# new_york_rev_B.net
KiCad netlist of a schematic drawn in EAGLE
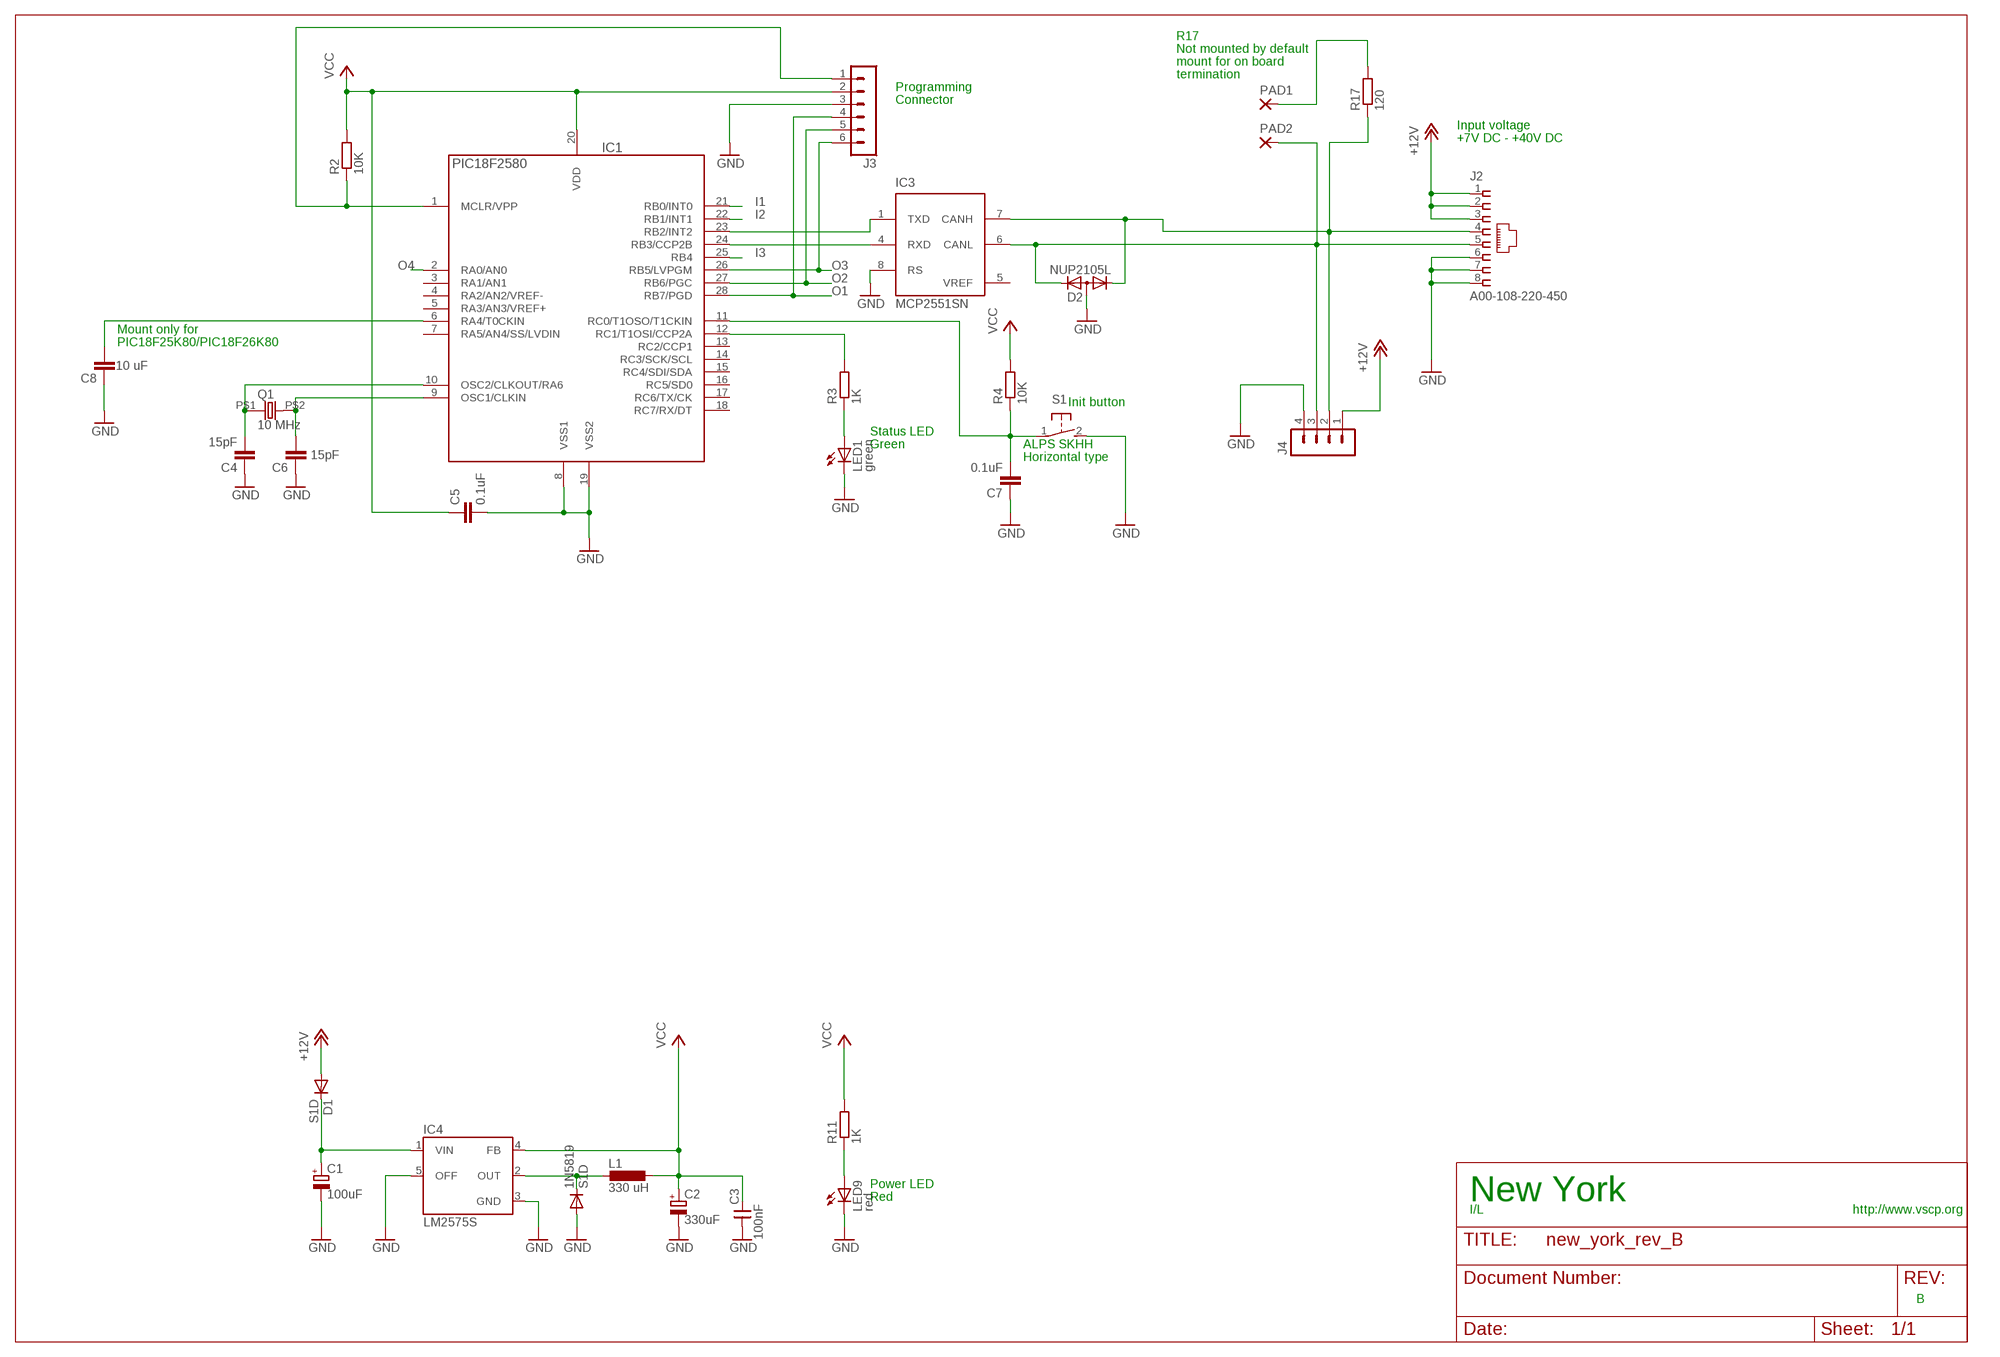
[diagram p0: schematic, sheet 1]

(export (version "E")
  (design (tool "Eeschema 10.0.6"))
  (components
    (comp (ref "1N5819")
      (value "S1D")
      (footprint "eagle-import:SOD123")
      (libsource (lib "eagle-import") (part "DIODE-SOD123"))
    )
    (comp (ref "C1")
      (value "100uF")
      (footprint "eagle-import:PANASONIC_D")
      (libsource (lib "eagle-import") (part "CPOL-EUD"))
    )
    (comp (ref "C2")
      (value "330uF")
      (footprint "eagle-import:PANASONIC_D")
      (libsource (lib "eagle-import") (part "CPOL-EUD"))
    )
    (comp (ref "C3")
      (value "100nF")
      (footprint "eagle-import:0805")
      (libsource (lib "eagle-import") (part "CNP-0805"))
    )
    (comp (ref "C4")
      (value "15pF")
      (footprint "eagle-import:C0805")
      (libsource (lib "eagle-import") (part "C-EUC0805"))
    )
    (comp (ref "C5")
      (value "0.1uF")
      (footprint "eagle-import:C0805")
      (libsource (lib "eagle-import") (part "C-EUC0805"))
    )
    (comp (ref "C6")
      (value "15pF")
      (footprint "eagle-import:C0805")
      (libsource (lib "eagle-import") (part "C-EUC0805"))
    )
    (comp (ref "C7")
      (value "0.1uF")
      (footprint "eagle-import:C0805")
      (libsource (lib "eagle-import") (part "C-EUC0805"))
    )
    (comp (ref "C8")
      (value "10 uF")
      (footprint "eagle-import:C0805")
      (libsource (lib "eagle-import") (part "C-EUC0805"))
    )
    (comp (ref "D1")
      (value "S1D")
      (footprint "eagle-import:SOD123")
      (libsource (lib "eagle-import") (part "DIODE-SOD123"))
    )
    (comp (ref "D2")
      (value "NUP2105L")
      (footprint "eagle-import:SOT23")
      (libsource (lib "eagle-import") (part "DIODE-2CA|ACSOT23"))
    )
    (comp (ref "IC1")
      (value "PIC18F2580")
      (footprint "eagle-import:SO28")
      (libsource (lib "eagle-import") (part "PIC18F252-?I/SOL"))
    )
    (comp (ref "IC3")
      (value "MCP2551SN")
      (footprint "eagle-import:SO-08")
      (libsource (lib "eagle-import") (part "MCP2551SN"))
    )
    (comp (ref "IC4")
      (value "LM2575S")
      (footprint "eagle-import:TO263-5")
      (libsource (lib "eagle-import") (part "LM2575S"))
    )
    (comp (ref "J2")
      (value "A00-108-220-450")
      (footprint "eagle-import:RJ-45")
      (libsource (lib "eagle-import") (part "A00-108-220-450"))
    )
    (comp (ref "J3")
      (value "MA06-1")
      (footprint "eagle-import:MA06-1")
      (libsource (lib "eagle-import") (part "MA06-1"))
    )
    (comp (ref "J4")
      (value "MA04-1")
      (footprint "eagle-import:MA04-1")
      (libsource (lib "eagle-import") (part "MA04-1"))
    )
    (comp (ref "L1")
      (value "330 uH")
      (footprint "eagle-import:DO3316P")
      (libsource (lib "eagle-import") (part "DO3316P"))
    )
    (comp (ref "LED1")
      (value "green")
      (footprint "eagle-import:CHIP-LED0805")
      (libsource (lib "eagle-import") (part "LEDCHIP-LED0805"))
    )
    (comp (ref "LED9")
      (value "red")
      (footprint "eagle-import:CHIP-LED0805")
      (libsource (lib "eagle-import") (part "LEDCHIP-LED0805"))
    )
    (comp (ref "PAD1")
      (value "1,6/0,8")
      (footprint "eagle-import:1,6_0,8")
      (libsource (lib "eagle-import") (part "1,6/0,8"))
    )
    (comp (ref "PAD2")
      (value "1,6/0,8")
      (footprint "eagle-import:1,6_0,8")
      (libsource (lib "eagle-import") (part "1,6/0,8"))
    )
    (comp (ref "Q1")
      (value "10 MHz")
      (footprint "eagle-import:9C")
      (libsource (lib "eagle-import") (part "HC-49S"))
    )
    (comp (ref "R2")
      (value "10K")
      (footprint "eagle-import:R0805")
      (libsource (lib "eagle-import") (part "R-EU_R0805"))
    )
    (comp (ref "R3")
      (value "1K")
      (footprint "eagle-import:R0805")
      (libsource (lib "eagle-import") (part "R-EU_R0805"))
    )
    (comp (ref "R4")
      (value "10K")
      (footprint "eagle-import:R0805")
      (libsource (lib "eagle-import") (part "R-EU_R0805"))
    )
    (comp (ref "R11")
      (value "1K")
      (footprint "eagle-import:R0805")
      (libsource (lib "eagle-import") (part "R-EU_R0805"))
    )
    (comp (ref "R17")
      (value "120")
      (footprint "eagle-import:R0805")
      (libsource (lib "eagle-import") (part "R-EU_R0805"))
    )
    (comp (ref "S1")
      (value "31-XX")
      (footprint "eagle-import:B3F-31XX")
      (fields (field (name "MPN") "B3F-3100"))
      (libsource (lib "eagle-import") (part "31-XX"))
    )
  )
  (nets
    (net (code "1") (name "+12V") (class "Default")
      (node (ref "D1") (pin "A") (pinfunction "A_A") (pintype "passive"))
      (node (ref "J2") (pin "1") (pinfunction "1_1") (pintype "passive"))
      (node (ref "J2") (pin "2") (pinfunction "2_2") (pintype "passive"))
      (node (ref "J2") (pin "3") (pinfunction "3_3") (pintype "passive"))
      (node (ref "J4") (pin "1") (pinfunction "1_1") (pintype "passive"))
    )
    (net (code "2") (name "/I1") (class "Default")
      (node (ref "IC1") (pin "21") (pinfunction "RB0/INT0_21") (pintype "bidirectional"))
    )
    (net (code "3") (name "/I2") (class "Default")
      (node (ref "IC1") (pin "22") (pinfunction "RB1/INT1_22") (pintype "bidirectional"))
    )
    (net (code "4") (name "/I3") (class "Default")
      (node (ref "IC1") (pin "25") (pinfunction "RB4_25") (pintype "bidirectional"))
    )
    (net (code "5") (name "/O1") (class "Default")
      (node (ref "IC1") (pin "28") (pinfunction "RB7/PGD_28") (pintype "bidirectional"))
      (node (ref "J3") (pin "4") (pinfunction "4_4") (pintype "passive"))
    )
    (net (code "6") (name "/O2") (class "Default")
      (node (ref "IC1") (pin "27") (pinfunction "RB6/PGC_27") (pintype "bidirectional"))
      (node (ref "J3") (pin "5") (pinfunction "5_5") (pintype "passive"))
    )
    (net (code "7") (name "/O3") (class "Default")
      (node (ref "IC1") (pin "26") (pinfunction "RB5/LVPGM_26") (pintype "bidirectional"))
      (node (ref "J3") (pin "6") (pinfunction "6_6") (pintype "passive"))
    )
    (net (code "8") (name "/O4") (class "Default")
      (node (ref "IC1") (pin "2") (pinfunction "RA0/AN0_2") (pintype "bidirectional"))
    )
    (net (code "9") (name "/VREF") (class "Default")
      (node (ref "IC3") (pin "5") (pinfunction "VREF_5") (pintype "power_in"))
    )
    (net (code "10") (name "GND") (class "Default")
      (node (ref "1N5819") (pin "A") (pinfunction "A_A") (pintype "passive"))
      (node (ref "C1") (pin "-") (pinfunction "-_-") (pintype "passive"))
      (node (ref "C2") (pin "-") (pinfunction "-_-") (pintype "passive"))
      (node (ref "C3") (pin "1") (pinfunction "1_1") (pintype "passive"))
      (node (ref "C4") (pin "1") (pinfunction "1_1") (pintype "passive"))
      (node (ref "C5") (pin "2") (pinfunction "2_2") (pintype "passive"))
      (node (ref "C6") (pin "1") (pinfunction "1_1") (pintype "passive"))
      (node (ref "C7") (pin "1") (pinfunction "1_1") (pintype "passive"))
      (node (ref "C8") (pin "1") (pinfunction "1_1") (pintype "passive"))
      (node (ref "D2") (pin "3") (pinfunction "A_3") (pintype "passive"))
      (node (ref "IC1") (pin "19") (pinfunction "VSS2_19") (pintype "power_in"))
      (node (ref "IC1") (pin "8") (pinfunction "VSS1_8") (pintype "power_in"))
      (node (ref "IC3") (pin "8") (pinfunction "RS_8") (pintype "input"))
      (node (ref "IC4") (pin "3") (pinfunction "GND_3") (pintype "power_in"))
      (node (ref "IC4") (pin "5") (pinfunction "OFF_5") (pintype "input"))
      (node (ref "J2") (pin "6") (pinfunction "6_6") (pintype "passive"))
      (node (ref "J2") (pin "7") (pinfunction "7_7") (pintype "passive"))
      (node (ref "J2") (pin "8") (pinfunction "8_8") (pintype "passive"))
      (node (ref "J3") (pin "3") (pinfunction "3_3") (pintype "passive"))
      (node (ref "J4") (pin "4") (pinfunction "4_4") (pintype "passive"))
      (node (ref "LED1") (pin "C") (pinfunction "C_C") (pintype "passive"))
      (node (ref "LED9") (pin "C") (pinfunction "C_C") (pintype "passive"))
      (node (ref "S1") (pin "2") (pinfunction "S_2") (pintype "passive"))
    )
    (net (code "11") (name "Net-(D2-K1)") (class "Default")
      (node (ref "D2") (pin "1") (pinfunction "K1_1") (pintype "passive"))
      (node (ref "IC3") (pin "7") (pinfunction "CANH_7") (pintype "bidirectional"))
      (node (ref "J2") (pin "4") (pinfunction "4_4") (pintype "passive"))
      (node (ref "J4") (pin "2") (pinfunction "2_2") (pintype "passive"))
      (node (ref "R17") (pin "1") (pinfunction "1_1") (pintype "passive"))
    )
    (net (code "12") (name "Net-(D2-K2)") (class "Default")
      (node (ref "D2") (pin "2") (pinfunction "K2_2") (pintype "passive"))
      (node (ref "IC3") (pin "6") (pinfunction "CANL_6") (pintype "bidirectional"))
      (node (ref "J2") (pin "5") (pinfunction "5_5") (pintype "passive"))
      (node (ref "J4") (pin "3") (pinfunction "3_3") (pintype "passive"))
      (node (ref "PAD2") (pin "1") (pinfunction "P_1") (pintype "passive"))
    )
    (net (code "13") (name "Net-(IC1-MCLR{slash}VPP)") (class "Default")
      (node (ref "IC1") (pin "1") (pinfunction "MCLR/VPP_1") (pintype "input"))
      (node (ref "J3") (pin "1") (pinfunction "1_1") (pintype "passive"))
      (node (ref "R2") (pin "1") (pinfunction "1_1") (pintype "passive"))
    )
    (net (code "14") (name "Net-(IC1-OSC1{slash}CLKIN)") (class "Default")
      (node (ref "C6") (pin "2") (pinfunction "2_2") (pintype "passive"))
      (node (ref "IC1") (pin "9") (pinfunction "OSC1/CLKIN_9") (pintype "input"))
      (node (ref "Q1") (pin "P$2") (pinfunction "2_P$2") (pintype "passive"))
    )
    (net (code "15") (name "Net-(IC1-OSC2{slash}CLKOUT{slash}RA6)") (class "Default")
      (node (ref "C4") (pin "2") (pinfunction "2_2") (pintype "passive"))
      (node (ref "IC1") (pin "10") (pinfunction "OSC2/CLKOUT/RA6_10") (pintype "output"))
      (node (ref "Q1") (pin "P$1") (pinfunction "1_P$1") (pintype "passive"))
    )
    (net (code "16") (name "Net-(IC1-RA4{slash}T0CKIN)") (class "Default")
      (node (ref "C8") (pin "2") (pinfunction "2_2") (pintype "passive"))
      (node (ref "IC1") (pin "6") (pinfunction "RA4/T0CKIN_6") (pintype "open_collector"))
    )
    (net (code "17") (name "Net-(IC1-RB2{slash}INT2)") (class "Default")
      (node (ref "IC1") (pin "23") (pinfunction "RB2/INT2_23") (pintype "bidirectional"))
      (node (ref "IC3") (pin "1") (pinfunction "TXD_1") (pintype "input"))
    )
    (net (code "18") (name "Net-(IC1-RB3{slash}CCP2B)") (class "Default")
      (node (ref "IC1") (pin "24") (pinfunction "RB3/CCP2B_24") (pintype "bidirectional"))
      (node (ref "IC3") (pin "4") (pinfunction "RXD_4") (pintype "output"))
    )
    (net (code "19") (name "Net-(IC1-RC0{slash}T1OSO{slash}T1CKIN)") (class "Default")
      (node (ref "C7") (pin "2") (pinfunction "2_2") (pintype "passive"))
      (node (ref "IC1") (pin "11") (pinfunction "RC0/T1OSO/T1CKIN_11") (pintype "bidirectional"))
      (node (ref "R4") (pin "1") (pinfunction "1_1") (pintype "passive"))
      (node (ref "S1") (pin "1") (pinfunction "P_1") (pintype "passive"))
    )
    (net (code "20") (name "Net-(IC1-RC1{slash}T1OSI{slash}CCP2A)") (class "Default")
      (node (ref "IC1") (pin "12") (pinfunction "RC1/T1OSI/CCP2A_12") (pintype "bidirectional"))
      (node (ref "R3") (pin "2") (pinfunction "2_2") (pintype "passive"))
    )
    (net (code "21") (name "Net-(IC4-OUT)") (class "Default")
      (node (ref "1N5819") (pin "C") (pinfunction "C_C") (pintype "passive"))
      (node (ref "IC4") (pin "2") (pinfunction "OUT_2") (pintype "output"))
      (node (ref "L1") (pin "1") (pinfunction "1_1") (pintype "passive"))
    )
    (net (code "22") (name "Net-(IC4-VIN)") (class "Default")
      (node (ref "C1") (pin "+") (pinfunction "+_+") (pintype "passive"))
      (node (ref "D1") (pin "C") (pinfunction "C_C") (pintype "passive"))
      (node (ref "IC4") (pin "1") (pinfunction "VIN_1") (pintype "power_in"))
    )
    (net (code "23") (name "Net-(LED1-PadA)") (class "Default")
      (node (ref "LED1") (pin "A") (pinfunction "A_A") (pintype "passive"))
      (node (ref "R3") (pin "1") (pinfunction "1_1") (pintype "passive"))
    )
    (net (code "24") (name "Net-(LED9-PadA)") (class "Default")
      (node (ref "LED9") (pin "A") (pinfunction "A_A") (pintype "passive"))
      (node (ref "R11") (pin "1") (pinfunction "1_1") (pintype "passive"))
    )
    (net (code "25") (name "Net-(PAD1-P)") (class "Default")
      (node (ref "PAD1") (pin "1") (pinfunction "P_1") (pintype "passive"))
      (node (ref "R17") (pin "2") (pinfunction "2_2") (pintype "passive"))
    )
    (net (code "26") (name "VCC") (class "Default")
      (node (ref "C2") (pin "+") (pinfunction "+_+") (pintype "passive"))
      (node (ref "C3") (pin "2") (pinfunction "2_2") (pintype "passive"))
      (node (ref "C5") (pin "1") (pinfunction "1_1") (pintype "passive"))
      (node (ref "IC1") (pin "20") (pinfunction "VDD_20") (pintype "power_in"))
      (node (ref "IC4") (pin "4") (pinfunction "FB_4") (pintype "input"))
      (node (ref "J3") (pin "2") (pinfunction "2_2") (pintype "passive"))
      (node (ref "L1") (pin "2") (pinfunction "2_2") (pintype "passive"))
      (node (ref "R11") (pin "2") (pinfunction "2_2") (pintype "passive"))
      (node (ref "R2") (pin "2") (pinfunction "2_2") (pintype "passive"))
      (node (ref "R4") (pin "2") (pinfunction "2_2") (pintype "passive"))
    )
    (net (code "27") (name "unconnected-(IC1-RA1{slash}AN1-Pad3)") (class "Default")
      (node (ref "IC1") (pin "3") (pinfunction "RA1/AN1_3") (pintype "bidirectional"))
    )
    (net (code "28") (name "unconnected-(IC1-RA2{slash}AN2{slash}VREF--Pad4)") (class "Default")
      (node (ref "IC1") (pin "4") (pinfunction "RA2/AN2/VREF-_4") (pintype "bidirectional"))
    )
    (net (code "29") (name "unconnected-(IC1-RA3{slash}AN3{slash}VREF+-Pad5)") (class "Default")
      (node (ref "IC1") (pin "5") (pinfunction "RA3/AN3/VREF+_5") (pintype "bidirectional"))
    )
    (net (code "30") (name "unconnected-(IC1-RA5{slash}AN4{slash}SS{slash}LVDIN-Pad7)") (class "Default")
      (node (ref "IC1") (pin "7") (pinfunction "RA5/AN4/SS/LVDIN_7") (pintype "bidirectional"))
    )
    (net (code "31") (name "unconnected-(IC1-RC2{slash}CCP1-Pad13)") (class "Default")
      (node (ref "IC1") (pin "13") (pinfunction "RC2/CCP1_13") (pintype "bidirectional"))
    )
    (net (code "32") (name "unconnected-(IC1-RC3{slash}SCK{slash}SCL-Pad14)") (class "Default")
      (node (ref "IC1") (pin "14") (pinfunction "RC3/SCK/SCL_14") (pintype "bidirectional"))
    )
    (net (code "33") (name "unconnected-(IC1-RC4{slash}SDI{slash}SDA-Pad15)") (class "Default")
      (node (ref "IC1") (pin "15") (pinfunction "RC4/SDI/SDA_15") (pintype "bidirectional"))
    )
    (net (code "34") (name "unconnected-(IC1-RC5{slash}SD0-Pad16)") (class "Default")
      (node (ref "IC1") (pin "16") (pinfunction "RC5/SD0_16") (pintype "bidirectional"))
    )
    (net (code "35") (name "unconnected-(IC1-RC6{slash}TX{slash}CK-Pad17)") (class "Default")
      (node (ref "IC1") (pin "17") (pinfunction "RC6/TX/CK_17") (pintype "bidirectional"))
    )
    (net (code "36") (name "unconnected-(IC1-RC7{slash}RX{slash}DT-Pad18)") (class "Default")
      (node (ref "IC1") (pin "18") (pinfunction "RC7/RX/DT_18") (pintype "bidirectional"))
    )
  )
)
